# Serializer.net
KiCad netlist of a schematic drawn in Altium Designer
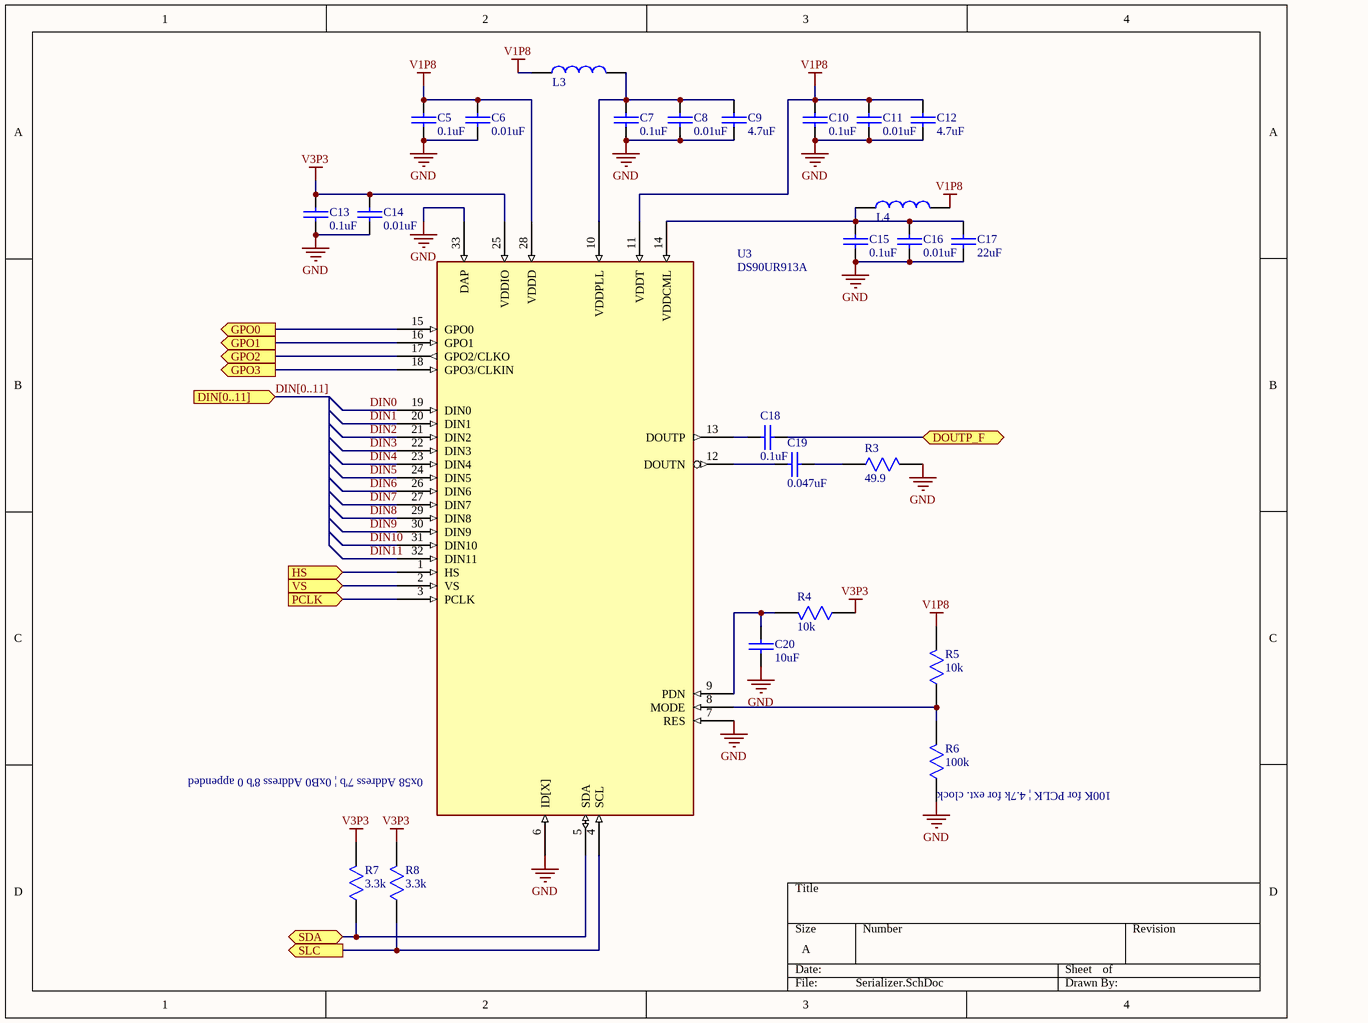
[diagram p0: Serializer.SchDoc]

(export (version "E")
  (design (tool "Eeschema 10.0.6"))
  (components
    (comp (ref "C5")
      (value "0.1uF")
      (footprint "SMD CAP 0402")
      (libsource (lib "DA_Component_Library") (part "Capacitor"))
    )
    (comp (ref "C6")
      (value "0.01uF")
      (footprint "SMD CAP 0402")
      (libsource (lib "DA_Component_Library") (part "Capacitor"))
    )
    (comp (ref "C7")
      (value "0.1uF")
      (footprint "SMD CAP 0402")
      (libsource (lib "DA_Component_Library") (part "Capacitor"))
    )
    (comp (ref "C8")
      (value "0.01uF")
      (footprint "SMD CAP 0402")
      (libsource (lib "DA_Component_Library") (part "Capacitor"))
    )
    (comp (ref "C9")
      (value "4.7uF")
      (footprint "SMD CAP 0402")
      (libsource (lib "DA_Component_Library") (part "Capacitor"))
    )
    (comp (ref "C10")
      (value "0.1uF")
      (footprint "SMD CAP 0402")
      (libsource (lib "DA_Component_Library") (part "Capacitor"))
    )
    (comp (ref "C11")
      (value "0.01uF")
      (footprint "SMD CAP 0402")
      (libsource (lib "DA_Component_Library") (part "Capacitor"))
    )
    (comp (ref "C12")
      (value "4.7uF")
      (footprint "SMD CAP 0402")
      (libsource (lib "DA_Component_Library") (part "Capacitor"))
    )
    (comp (ref "C13")
      (value "0.1uF")
      (footprint "SMD CAP 0402")
      (libsource (lib "DA_Component_Library") (part "Capacitor"))
    )
    (comp (ref "C14")
      (value "0.01uF")
      (footprint "SMD CAP 0402")
      (libsource (lib "DA_Component_Library") (part "Capacitor"))
    )
    (comp (ref "C15")
      (value "0.1uF")
      (footprint "SMD CAP 0402")
      (libsource (lib "DA_Component_Library") (part "Capacitor"))
    )
    (comp (ref "C16")
      (value "0.01uF")
      (footprint "SMD CAP 0402")
      (libsource (lib "DA_Component_Library") (part "Capacitor"))
    )
    (comp (ref "C17")
      (value "22uF")
      (footprint "SMD Capacitor 0603")
      (libsource (lib "DA_Component_Library") (part "Capacitor"))
    )
    (comp (ref "C18")
      (value "0.1uF")
      (footprint "SMD CAP 0402")
      (libsource (lib "DA_Component_Library") (part "Capacitor"))
    )
    (comp (ref "C19")
      (value "0.047uF")
      (footprint "SMD CAP 0402")
      (libsource (lib "DA_Component_Library") (part "Capacitor"))
    )
    (comp (ref "C20")
      (value "10uF")
      (footprint "SMD CAP 0402")
      (libsource (lib "DA_Component_Library") (part "Capacitor"))
    )
    (comp (ref "L3")
      (value "Ferrite Bead")
      (footprint "BLM18KG601SN1D")
      (libsource (lib "DA_Component_Library") (part "Ferrite Bead"))
    )
    (comp (ref "L4")
      (value "Ferrite Bead")
      (footprint "BLM18KG601SN1D")
      (libsource (lib "DA_Component_Library") (part "Ferrite Bead"))
    )
    (comp (ref "R3")
      (value "49.9")
      (footprint "SMD RES 0402")
      (libsource (lib "DA_Component_Library") (part "Resistor"))
    )
    (comp (ref "R4")
      (value "10k")
      (footprint "SMD RES 0402")
      (libsource (lib "DA_Component_Library") (part "Resistor"))
    )
    (comp (ref "R5")
      (value "10k")
      (footprint "SMD RES 0402")
      (libsource (lib "DA_Component_Library") (part "Resistor"))
    )
    (comp (ref "R6")
      (value "100k")
      (footprint "SMD RES 0402")
      (libsource (lib "DA_Component_Library") (part "Resistor"))
    )
    (comp (ref "R7")
      (value "3.3k")
      (footprint "SMD RES 0402")
      (libsource (lib "DA_Component_Library") (part "Resistor"))
    )
    (comp (ref "R8")
      (value "3.3k")
      (footprint "SMD RES 0402")
      (libsource (lib "DA_Component_Library") (part "Resistor"))
    )
    (comp (ref "U3")
      (value "DS90UR913A")
      (footprint "WQFN32 for DS90UB913A")
      (description "DS90UR913ASERIALIZER")
      (libsource (lib "DA_Component_Library") (part "DS90UR913A"))
    )
  )
  (nets
    (net (code "1") (name "/DIN0") (class "Default")
      (node (ref "U3") (pin "19") (pinfunction "DIN0_19") (pintype "input"))
    )
    (net (code "2") (name "/DIN1") (class "Default")
      (node (ref "U3") (pin "20") (pinfunction "DIN1_20") (pintype "input"))
    )
    (net (code "3") (name "/DIN2") (class "Default")
      (node (ref "U3") (pin "21") (pinfunction "DIN2_21") (pintype "input"))
    )
    (net (code "4") (name "/DIN3") (class "Default")
      (node (ref "U3") (pin "22") (pinfunction "DIN3_22") (pintype "input"))
    )
    (net (code "5") (name "/DIN4") (class "Default")
      (node (ref "U3") (pin "23") (pinfunction "DIN4_23") (pintype "input"))
    )
    (net (code "6") (name "/DIN5") (class "Default")
      (node (ref "U3") (pin "24") (pinfunction "DIN5_24") (pintype "input"))
    )
    (net (code "7") (name "/DIN6") (class "Default")
      (node (ref "U3") (pin "26") (pinfunction "DIN6_26") (pintype "input"))
    )
    (net (code "8") (name "/DIN7") (class "Default")
      (node (ref "U3") (pin "27") (pinfunction "DIN7_27") (pintype "input"))
    )
    (net (code "9") (name "/DIN8") (class "Default")
      (node (ref "U3") (pin "29") (pinfunction "DIN8_29") (pintype "input"))
    )
    (net (code "10") (name "/DIN9") (class "Default")
      (node (ref "U3") (pin "30") (pinfunction "DIN9_30") (pintype "input"))
    )
    (net (code "11") (name "/DIN10") (class "Default")
      (node (ref "U3") (pin "31") (pinfunction "DIN10_31") (pintype "input"))
    )
    (net (code "12") (name "/DIN11") (class "Default")
      (node (ref "U3") (pin "32") (pinfunction "DIN11_32") (pintype "input"))
    )
    (net (code "14") (name "/DOUTP_F") (class "Default")
      (node (ref "C18") (pin "1") (pinfunction "1_1") (pintype "passive"))
    )
    (net (code "15") (name "/GPO0") (class "Default")
      (node (ref "U3") (pin "15") (pinfunction "GPO0_15") (pintype "input"))
    )
    (net (code "16") (name "/GPO1") (class "Default")
      (node (ref "U3") (pin "16") (pinfunction "GPO1_16") (pintype "input"))
    )
    (net (code "17") (name "/GPO2") (class "Default")
      (node (ref "U3") (pin "17") (pinfunction "GPO2/CLKO_17") (pintype "output"))
    )
    (net (code "18") (name "/GPO3") (class "Default")
      (node (ref "U3") (pin "18") (pinfunction "GPO3/CLKIN_18") (pintype "input"))
    )
    (net (code "19") (name "/HS") (class "Default")
      (node (ref "U3") (pin "1") (pinfunction "HS_1") (pintype "input"))
    )
    (net (code "20") (name "/PCLK") (class "Default")
      (node (ref "U3") (pin "3") (pinfunction "PCLK_3") (pintype "input"))
    )
    (net (code "21") (name "/SDA") (class "Default")
      (node (ref "R7") (pin "0") (pinfunction "0_0") (pintype "passive"))
      (node (ref "U3") (pin "5") (pinfunction "SDA_5") (pintype "bidirectional"))
    )
    (net (code "22") (name "/SLC") (class "Default")
      (node (ref "R8") (pin "0") (pinfunction "0_0") (pintype "passive"))
      (node (ref "U3") (pin "4") (pinfunction "SCL_4") (pintype "input"))
    )
    (net (code "23") (name "/VS") (class "Default")
      (node (ref "U3") (pin "2") (pinfunction "VS_2") (pintype "input"))
    )
    (net (code "24") (name "GND") (class "Default")
      (node (ref "C10") (pin "1") (pinfunction "1_1") (pintype "passive"))
      (node (ref "C11") (pin "1") (pinfunction "1_1") (pintype "passive"))
      (node (ref "C12") (pin "1") (pinfunction "1_1") (pintype "passive"))
      (node (ref "C13") (pin "1") (pinfunction "1_1") (pintype "passive"))
      (node (ref "C14") (pin "1") (pinfunction "1_1") (pintype "passive"))
      (node (ref "C15") (pin "1") (pinfunction "1_1") (pintype "passive"))
      (node (ref "C16") (pin "1") (pinfunction "1_1") (pintype "passive"))
      (node (ref "C17") (pin "1") (pinfunction "1_1") (pintype "passive"))
      (node (ref "C20") (pin "1") (pinfunction "1_1") (pintype "passive"))
      (node (ref "C5") (pin "1") (pinfunction "1_1") (pintype "passive"))
      (node (ref "C6") (pin "1") (pinfunction "1_1") (pintype "passive"))
      (node (ref "C7") (pin "1") (pinfunction "1_1") (pintype "passive"))
      (node (ref "C8") (pin "1") (pinfunction "1_1") (pintype "passive"))
      (node (ref "C9") (pin "1") (pinfunction "1_1") (pintype "passive"))
      (node (ref "R3") (pin "1") (pinfunction "1_1") (pintype "passive"))
      (node (ref "R6") (pin "0") (pinfunction "0_0") (pintype "passive"))
      (node (ref "U3") (pin "33") (pinfunction "DAP_33") (pintype "input"))
      (node (ref "U3") (pin "6") (pinfunction "ID[X]_6") (pintype "input"))
      (node (ref "U3") (pin "7") (pinfunction "RES_7") (pintype "input"))
    )
    (net (code "25") (name "Net-(C19-Pad1)") (class "Default")
      (node (ref "C19") (pin "1") (pinfunction "1_1") (pintype "passive"))
      (node (ref "R3") (pin "0") (pinfunction "0_0") (pintype "passive"))
    )
    (net (code "26") (name "Net-(U3-DOUTN)") (class "Default")
      (node (ref "C19") (pin "0") (pinfunction "0_0") (pintype "passive"))
      (node (ref "U3") (pin "12") (pinfunction "DOUTN_12") (pintype "output"))
    )
    (net (code "27") (name "Net-(U3-DOUTP)") (class "Default")
      (node (ref "C18") (pin "0") (pinfunction "0_0") (pintype "passive"))
      (node (ref "U3") (pin "13") (pinfunction "DOUTP_13") (pintype "output"))
    )
    (net (code "28") (name "Net-(U3-MODE)") (class "Default")
      (node (ref "R5") (pin "0") (pinfunction "0_0") (pintype "passive"))
      (node (ref "R6") (pin "1") (pinfunction "1_1") (pintype "passive"))
      (node (ref "U3") (pin "8") (pinfunction "MODE_8") (pintype "input"))
    )
    (net (code "29") (name "Net-(U3-PDN)") (class "Default")
      (node (ref "C20") (pin "0") (pinfunction "0_0") (pintype "passive"))
      (node (ref "R4") (pin "1") (pinfunction "1_1") (pintype "passive"))
      (node (ref "U3") (pin "9") (pinfunction "PDN_9") (pintype "input"))
    )
    (net (code "30") (name "Net-(U3-VDDCML)") (class "Default")
      (node (ref "C15") (pin "0") (pinfunction "0_0") (pintype "passive"))
      (node (ref "C16") (pin "0") (pinfunction "0_0") (pintype "passive"))
      (node (ref "C17") (pin "0") (pinfunction "0_0") (pintype "passive"))
      (node (ref "L4") (pin "1") (pinfunction "1_1") (pintype "passive"))
      (node (ref "U3") (pin "14") (pinfunction "VDDCML_14") (pintype "input"))
    )
    (net (code "31") (name "Net-(U3-VDDPLL)") (class "Default")
      (node (ref "C7") (pin "0") (pinfunction "0_0") (pintype "passive"))
      (node (ref "C8") (pin "0") (pinfunction "0_0") (pintype "passive"))
      (node (ref "C9") (pin "0") (pinfunction "0_0") (pintype "passive"))
      (node (ref "L3") (pin "2") (pinfunction "2_2") (pintype "passive"))
      (node (ref "U3") (pin "10") (pinfunction "VDDPLL_10") (pintype "input"))
    )
    (net (code "32") (name "V1P8") (class "Default")
      (node (ref "C10") (pin "0") (pinfunction "0_0") (pintype "passive"))
      (node (ref "C11") (pin "0") (pinfunction "0_0") (pintype "passive"))
      (node (ref "C12") (pin "0") (pinfunction "0_0") (pintype "passive"))
      (node (ref "C5") (pin "0") (pinfunction "0_0") (pintype "passive"))
      (node (ref "C6") (pin "0") (pinfunction "0_0") (pintype "passive"))
      (node (ref "L3") (pin "1") (pinfunction "1_1") (pintype "passive"))
      (node (ref "L4") (pin "2") (pinfunction "2_2") (pintype "passive"))
      (node (ref "R5") (pin "1") (pinfunction "1_1") (pintype "passive"))
      (node (ref "U3") (pin "11") (pinfunction "VDDT_11") (pintype "input"))
      (node (ref "U3") (pin "28") (pinfunction "VDDD_28") (pintype "input"))
    )
    (net (code "33") (name "V3P3") (class "Default")
      (node (ref "C13") (pin "0") (pinfunction "0_0") (pintype "passive"))
      (node (ref "C14") (pin "0") (pinfunction "0_0") (pintype "passive"))
      (node (ref "R4") (pin "0") (pinfunction "0_0") (pintype "passive"))
      (node (ref "R7") (pin "1") (pinfunction "1_1") (pintype "passive"))
      (node (ref "R8") (pin "1") (pinfunction "1_1") (pintype "passive"))
      (node (ref "U3") (pin "25") (pinfunction "VDDIO_25") (pintype "input"))
    )
  )
)
